# uC.net
KiCad netlist of a schematic drawn in Altium Designer
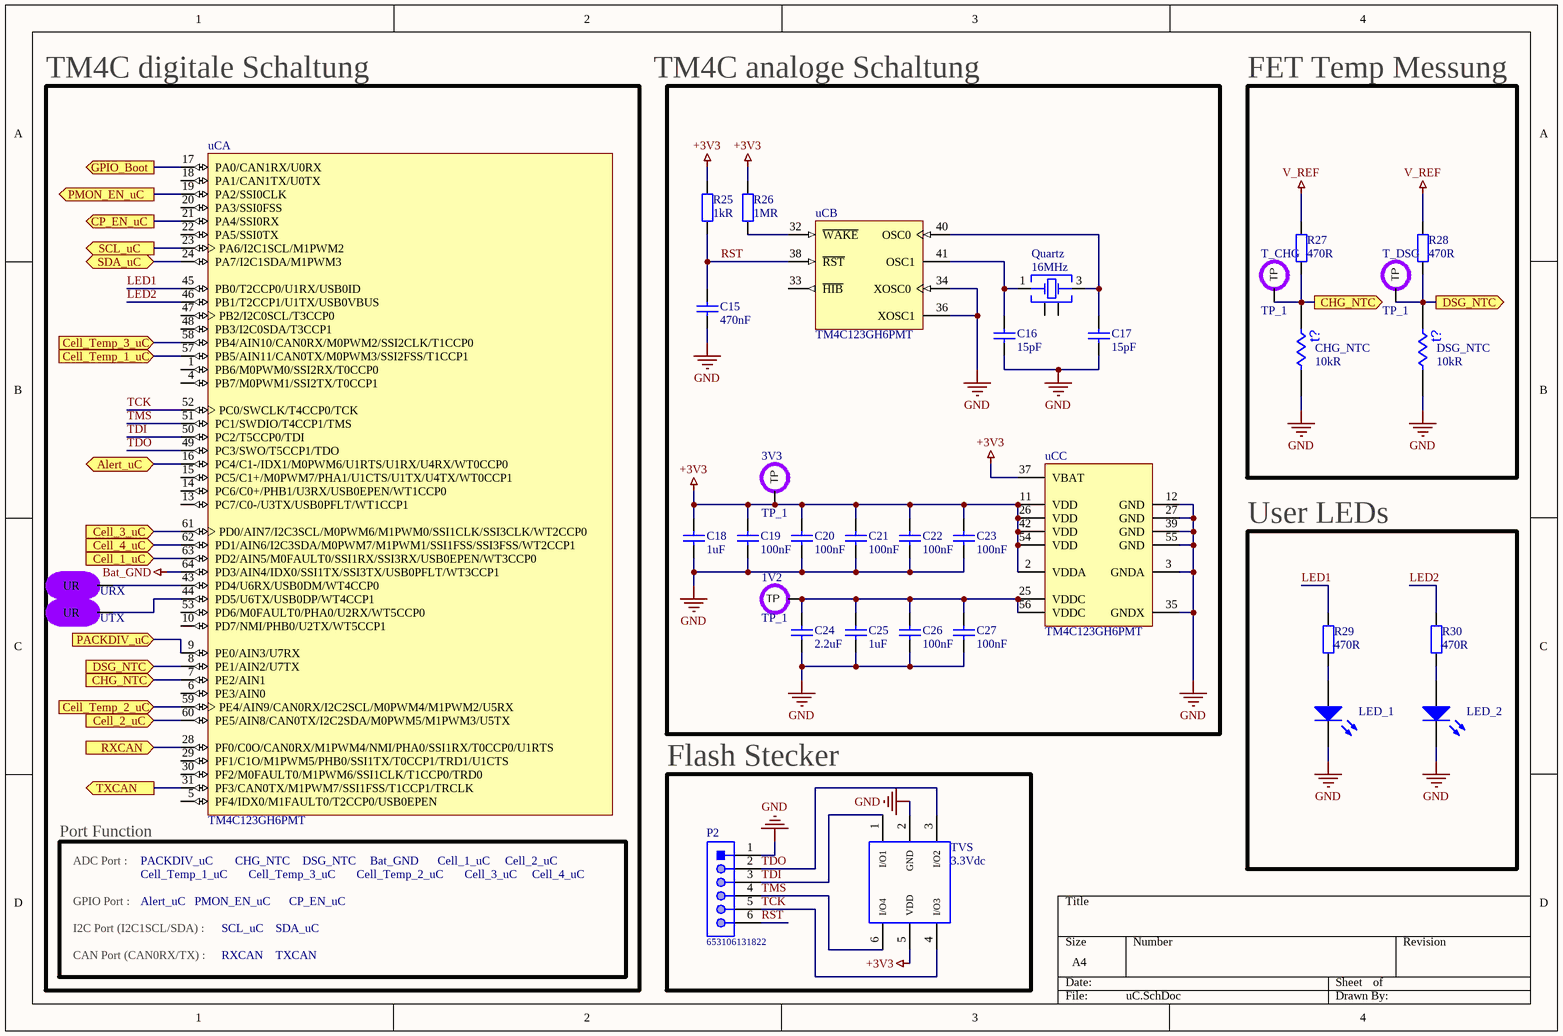
[diagram p0: uC.SchDoc]

(export (version "E")
  (design (tool "Eeschema 10.0.6"))
  (components
    (comp (ref "1V2")
      (value "TP_1")
      (footprint "Test point")
      (description "Power Supply for logical circuit")
      (libsource (lib "Schlib1") (part "Test point"))
    )
    (comp (ref "3V3")
      (value "TP_1")
      (footprint "Test point")
      (description "Power Supply for uC")
      (libsource (lib "Schlib1") (part "Test point"))
    )
    (comp (ref "C15")
      (value "470nF")
      (footprint "1608[0603]")
      (description "Capacitor")
      (fields (field (name "PUBLISHER") "Altium Limited"))
      (libsource (lib "Miscellaneous Devices") (part "Cap"))
    )
    (comp (ref "C16")
      (value "15pF")
      (footprint "1608[0603]")
      (description "Capacitor")
      (fields (field (name "PUBLISHER") "Altium Limited"))
      (libsource (lib "Miscellaneous Devices") (part "Cap"))
    )
    (comp (ref "C17")
      (value "15pF")
      (footprint "1608[0603]")
      (description "Capacitor")
      (fields (field (name "PUBLISHER") "Altium Limited"))
      (libsource (lib "Miscellaneous Devices") (part "Cap"))
    )
    (comp (ref "C18")
      (value "1uF")
      (footprint "1608[0603]")
      (description "Capacitor")
      (fields (field (name "PUBLISHER") "Altium Limited"))
      (libsource (lib "Miscellaneous Devices") (part "Cap"))
    )
    (comp (ref "C19")
      (value "100nF")
      (footprint "1608[0603]")
      (description "Capacitor")
      (fields (field (name "PUBLISHER") "Altium Limited"))
      (libsource (lib "Miscellaneous Devices") (part "Cap"))
    )
    (comp (ref "C20")
      (value "100nF")
      (footprint "1608[0603]")
      (description "Capacitor")
      (fields (field (name "PUBLISHER") "Altium Limited"))
      (libsource (lib "Miscellaneous Devices") (part "Cap"))
    )
    (comp (ref "C21")
      (value "100nF")
      (footprint "1608[0603]")
      (description "Capacitor")
      (fields (field (name "PUBLISHER") "Altium Limited"))
      (libsource (lib "Miscellaneous Devices") (part "Cap"))
    )
    (comp (ref "C22")
      (value "100nF")
      (footprint "1608[0603]")
      (description "Capacitor")
      (fields (field (name "PUBLISHER") "Altium Limited"))
      (libsource (lib "Miscellaneous Devices") (part "Cap"))
    )
    (comp (ref "C23")
      (value "100nF")
      (footprint "1608[0603]")
      (description "Capacitor")
      (fields (field (name "PUBLISHER") "Altium Limited"))
      (libsource (lib "Miscellaneous Devices") (part "Cap"))
    )
    (comp (ref "C24")
      (value "2.2uF")
      (footprint "1608[0603]")
      (description "Capacitor")
      (fields (field (name "PUBLISHER") "Altium Limited"))
      (libsource (lib "Miscellaneous Devices") (part "Cap"))
    )
    (comp (ref "C25")
      (value "1uF")
      (footprint "1608[0603]")
      (description "Capacitor")
      (fields (field (name "PUBLISHER") "Altium Limited"))
      (libsource (lib "Miscellaneous Devices") (part "Cap"))
    )
    (comp (ref "C26")
      (value "100nF")
      (footprint "1608[0603]")
      (description "Capacitor")
      (fields (field (name "PUBLISHER") "Altium Limited"))
      (libsource (lib "Miscellaneous Devices") (part "Cap"))
    )
    (comp (ref "C27")
      (value "100nF")
      (footprint "1608[0603]")
      (description "Capacitor")
      (fields (field (name "PUBLISHER") "Altium Limited"))
      (libsource (lib "Miscellaneous Devices") (part "Cap"))
    )
    (comp (ref "CHG_NTC")
      (value "10kR")
      (footprint "J1-0603")
      (description "Thermistor")
      (fields (field (name "PUBLISHER") "Altium Limited"))
      (libsource (lib "Miscellaneous Devices") (part "Res Thermal"))
    )
    (comp (ref "DSG_NTC")
      (value "10kR")
      (footprint "J1-0603")
      (description "Thermistor")
      (fields (field (name "PUBLISHER") "Altium Limited"))
      (libsource (lib "Miscellaneous Devices") (part "Res Thermal"))
    )
    (comp (ref "LED_1")
      (value "~")
      (footprint "1608[0603]")
      (description "Typical INFRARED GaAs LED")
      (fields (field (name "PUBLISHER") "Altium Limited"))
      (libsource (lib "Miscellaneous Devices") (part "LED0"))
    )
    (comp (ref "LED_2")
      (value "~")
      (footprint "1608[0603]")
      (description "Typical INFRARED GaAs LED")
      (fields (field (name "PUBLISHER") "Altium Limited"))
      (libsource (lib "Miscellaneous Devices") (part "LED0"))
    )
    (comp (ref "P2")
      (value "653106131822")
      (footprint "653106131822")
      (description "Male Shrouded Header WR-WTB, SMT, Right Angled, pitch 1.25 mm, 1 x 6 position")
      (fields (field (name "MANUFACTURER") "Wurth Elektronik") (field (name "PUBLISHER") "WurthElektronik"))
      (libsource (lib "Altium Content Vault") (part "WE-CN-1P-M-R6"))
    )
    (comp (ref "Quartz")
      (value "16MHz")
      (footprint "WE-XTAL_CFPX-180")
      (description "WE-XTAL Quartz Crystal, SMT, CFPX-180, 16MHz, +/-10ppm")
      (fields
        (field (name "MANUFACTURER PART NUMBER") "830108207109")
        (field (name "MANUFACTURER") "Wurth Elektronik")
      )
      (libsource (lib "Quartz Altium_WE-XTAL+(rev20c)") (part "830108207109"))
    )
    (comp (ref "R25")
      (value "1kR")
      (footprint "J1-0603")
      (description "Resistor")
      (fields (field (name "PUBLISHER") "Altium Limited"))
      (libsource (lib "") (part "Res2_1"))
    )
    (comp (ref "R26")
      (value "1MR")
      (footprint "J1-0603")
      (description "Resistor")
      (fields (field (name "PUBLISHER") "Altium Limited"))
      (libsource (lib "") (part "Res2_1"))
    )
    (comp (ref "R27")
      (value "470R")
      (footprint "J1-0603")
      (description "Resistor")
      (fields (field (name "PUBLISHER") "Altium Limited"))
      (libsource (lib "Miscellaneous Devices") (part "Res2"))
    )
    (comp (ref "R28")
      (value "470R")
      (footprint "J1-0603")
      (description "Resistor")
      (fields (field (name "PUBLISHER") "Altium Limited"))
      (libsource (lib "Miscellaneous Devices") (part "Res2"))
    )
    (comp (ref "R29")
      (value "470R")
      (footprint "J1-0603")
      (description "Resistor")
      (fields (field (name "PUBLISHER") "Altium Limited"))
      (libsource (lib "") (part "Res2_1"))
    )
    (comp (ref "R30")
      (value "470R")
      (footprint "J1-0603")
      (description "Resistor")
      (fields (field (name "PUBLISHER") "Altium Limited"))
      (libsource (lib "") (part "Res2_1"))
    )
    (comp (ref "TVS")
      (value "3.3Vdc")
      (footprint "WE-TVS_SOT23-6L")
      (description "WE-TVS TVS Diode - High Speed Series, SOT23-6L, 4+1Channel, 3.3Vdc")
      (fields
        (field (name "MANUFACTURER PART NUMBER") "824013")
        (field (name "MANUFACTURER") "Wurth Elektronik")
      )
      (libsource (lib "Altium_WE-TVS (rev20a)") (part "824013"))
    )
    (comp (ref "T_CHG")
      (value "TP_1")
      (footprint "Test point")
      (libsource (lib "Schlib1") (part "Test point"))
    )
    (comp (ref "T_DSG")
      (value "TP_1")
      (footprint "Test point")
      (libsource (lib "Schlib1") (part "Test point"))
    )
    (comp (ref "uC")
      (value "TM4C123GH6PMT")
      (footprint "PM0064A_L")
      (fields (field (name "MANUFACTURER") "Texas Instruments"))
      (libsource (lib "Altium Content Vault") (part "TI-TM4C123GH6PM-LQFP-64"))
    )
    (comp (ref "URX") (value "UR") (footprint "UR Pad") (libsource (lib "Schlib1") (part "UR Pad")))
    (comp (ref "UTX") (value "UR") (footprint "UR Pad") (libsource (lib "Schlib1") (part "UR Pad")))
  )
  (nets
    (net (code "1") (name "+3V3") (class "Default")
      (node (ref "3V3") (pin "1") (pinfunction "TP_1") (pintype "passive"))
      (node (ref "C18") (pin "1") (pinfunction "1_1") (pintype "passive"))
      (node (ref "C19") (pin "1") (pinfunction "1_1") (pintype "passive"))
      (node (ref "C20") (pin "1") (pinfunction "1_1") (pintype "passive"))
      (node (ref "C21") (pin "1") (pinfunction "1_1") (pintype "passive"))
      (node (ref "C22") (pin "1") (pinfunction "1_1") (pintype "passive"))
      (node (ref "C23") (pin "1") (pinfunction "1_1") (pintype "passive"))
      (node (ref "R25") (pin "1") (pinfunction "1_1") (pintype "passive"))
      (node (ref "R26") (pin "1") (pinfunction "1_1") (pintype "passive"))
      (node (ref "TVS") (pin "5") (pinfunction "VDD_5") (pintype "passive"))
      (node (ref "uC") (pin "11") (pinfunction "VDD_11") (pintype "power_in"))
      (node (ref "uC") (pin "2") (pinfunction "VDDA_2") (pintype "power_in"))
      (node (ref "uC") (pin "26") (pinfunction "VDD_26") (pintype "power_in"))
      (node (ref "uC") (pin "37") (pinfunction "VBAT_37") (pintype "power_in"))
      (node (ref "uC") (pin "42") (pinfunction "VDD_42") (pintype "power_in"))
      (node (ref "uC") (pin "54") (pinfunction "VDD_54") (pintype "power_in"))
    )
    (net (code "2") (name "/Alert_uC") (class "Default")
      (node (ref "uC") (pin "16") (pinfunction "PC4/C1-/IDX1/M0PWM6/U1RTS/U1RX/U4RX/WT0CCP0_16") (pintype "bidirectional"))
    )
    (net (code "3") (name "/CHG_NTC") (class "Default")
      (node (ref "CHG_NTC") (pin "1") (pinfunction "1_1") (pintype "passive"))
      (node (ref "R27") (pin "2") (pinfunction "2_2") (pintype "passive"))
      (node (ref "T_CHG") (pin "1") (pinfunction "TP_1") (pintype "passive"))
      (node (ref "uC") (pin "7") (pinfunction "PE2/AIN1_7") (pintype "bidirectional"))
    )
    (net (code "4") (name "/CP_EN_uC") (class "Default")
      (node (ref "uC") (pin "21") (pinfunction "PA4/SSI0RX_21") (pintype "bidirectional"))
    )
    (net (code "5") (name "/Cell_1_uC") (class "Default")
      (node (ref "uC") (pin "63") (pinfunction "PD2/AIN5/M0FAULT0/SSI1RX/SSI3RX/USB0EPEN/WT3CCP0_63") (pintype "bidirectional"))
    )
    (net (code "6") (name "/Cell_2_uC") (class "Default")
      (node (ref "uC") (pin "60") (pinfunction "PE5/AIN8/CAN0TX/I2C2SDA/M0PWM5/M1PWM3/U5TX_60") (pintype "bidirectional"))
    )
    (net (code "7") (name "/Cell_3_uC") (class "Default")
      (node (ref "uC") (pin "61") (pinfunction "PD0/AIN7/I2C3SCL/M0PWM6/M1PWM0/SSI1CLK/SSI3CLK/WT2CCP0_61") (pintype "bidirectional"))
    )
    (net (code "8") (name "/Cell_4_uC") (class "Default")
      (node (ref "uC") (pin "62") (pinfunction "PD1/AIN6/I2C3SDA/M0PWM7/M1PWM1/SSI1FSS/SSI3FSS/WT2CCP1_62") (pintype "bidirectional"))
    )
    (net (code "9") (name "/Cell_Temp_1_uC") (class "Default")
      (node (ref "uC") (pin "57") (pinfunction "PB5/AIN11/CAN0TX/M0PWM3/SSI2FSS/T1CCP1_57") (pintype "bidirectional"))
    )
    (net (code "10") (name "/Cell_Temp_2_uC") (class "Default")
      (node (ref "uC") (pin "59") (pinfunction "PE4/AIN9/CAN0RX/I2C2SCL/M0PWM4/M1PWM2/U5RX_59") (pintype "bidirectional"))
    )
    (net (code "11") (name "/Cell_Temp_3_uC") (class "Default")
      (node (ref "uC") (pin "58") (pinfunction "PB4/AIN10/CAN0RX/M0PWM2/SSI2CLK/T1CCP0_58") (pintype "bidirectional"))
    )
    (net (code "12") (name "/DSG_NTC") (class "Default")
      (node (ref "DSG_NTC") (pin "1") (pinfunction "1_1") (pintype "passive"))
      (node (ref "R28") (pin "2") (pinfunction "2_2") (pintype "passive"))
      (node (ref "T_DSG") (pin "1") (pinfunction "TP_1") (pintype "passive"))
      (node (ref "uC") (pin "8") (pinfunction "PE1/AIN2/U7TX_8") (pintype "bidirectional"))
    )
    (net (code "13") (name "/GPIO_Boot") (class "Default")
      (node (ref "uC") (pin "17") (pinfunction "PA0/CAN1RX/U0RX_17") (pintype "bidirectional"))
    )
    (net (code "14") (name "/LED1") (class "Default")
      (node (ref "R29") (pin "1") (pinfunction "1_1") (pintype "passive"))
      (node (ref "uC") (pin "45") (pinfunction "PB0/T2CCP0/U1RX/USB0ID_45") (pintype "bidirectional"))
    )
    (net (code "15") (name "/LED2") (class "Default")
      (node (ref "R30") (pin "1") (pinfunction "1_1") (pintype "passive"))
      (node (ref "uC") (pin "46") (pinfunction "PB1/T2CCP1/U1TX/USB0VBUS_46") (pintype "bidirectional"))
    )
    (net (code "16") (name "/PACKDIV_uC") (class "Default")
      (node (ref "uC") (pin "9") (pinfunction "PE0/AIN3/U7RX_9") (pintype "bidirectional"))
    )
    (net (code "17") (name "/PMON_EN_uC") (class "Default")
      (node (ref "uC") (pin "19") (pinfunction "PA2/SSI0CLK_19") (pintype "bidirectional"))
    )
    (net (code "18") (name "/RST") (class "Default")
      (node (ref "C15") (pin "1") (pinfunction "1_1") (pintype "passive"))
      (node (ref "P2") (pin "6") (pinfunction "6_6") (pintype "passive"))
      (node (ref "R25") (pin "2") (pinfunction "2_2") (pintype "passive"))
      (node (ref "uC") (pin "38") (pinfunction "~{RST}_38") (pintype "input"))
    )
    (net (code "19") (name "/RXCAN") (class "Default")
      (node (ref "uC") (pin "28") (pinfunction "PF0/C0O/CAN0RX/M1PWM4/NMI/PHA0/SSI1RX/T0CCP0/U1RTS_28") (pintype "bidirectional"))
    )
    (net (code "20") (name "/SCL_uC") (class "Default")
      (node (ref "uC") (pin "23") (pinfunction "PA6/I2C1SCL/M1PWM2_23") (pintype "bidirectional"))
    )
    (net (code "21") (name "/SDA_uC") (class "Default")
      (node (ref "uC") (pin "24") (pinfunction "PA7/I2C1SDA/M1PWM3_24") (pintype "bidirectional"))
    )
    (net (code "22") (name "/TCK") (class "Default")
      (node (ref "P2") (pin "5") (pinfunction "5_5") (pintype "passive"))
      (node (ref "TVS") (pin "4") (pinfunction "I/O3_4") (pintype "passive"))
      (node (ref "uC") (pin "52") (pinfunction "PC0/SWCLK/T4CCP0/TCK_52") (pintype "bidirectional"))
    )
    (net (code "23") (name "/TDI") (class "Default")
      (node (ref "P2") (pin "3") (pinfunction "3_3") (pintype "passive"))
      (node (ref "TVS") (pin "1") (pinfunction "I/O1_1") (pintype "passive"))
      (node (ref "uC") (pin "50") (pinfunction "PC2/T5CCP0/TDI_50") (pintype "bidirectional"))
    )
    (net (code "24") (name "/TDO") (class "Default")
      (node (ref "P2") (pin "2") (pinfunction "2_2") (pintype "passive"))
      (node (ref "TVS") (pin "3") (pinfunction "I/O2_3") (pintype "passive"))
      (node (ref "uC") (pin "49") (pinfunction "PC3/SWO/T5CCP1/TDO_49") (pintype "bidirectional"))
    )
    (net (code "25") (name "/TMS") (class "Default")
      (node (ref "P2") (pin "4") (pinfunction "4_4") (pintype "passive"))
      (node (ref "TVS") (pin "6") (pinfunction "I/O4_6") (pintype "passive"))
      (node (ref "uC") (pin "51") (pinfunction "PC1/SWDIO/T4CCP1/TMS_51") (pintype "bidirectional"))
    )
    (net (code "26") (name "/TXCAN") (class "Default")
      (node (ref "uC") (pin "31") (pinfunction "PF3/CAN0TX/M1PWM7/SSI1FSS/T1CCP1/TRCLK_31") (pintype "bidirectional"))
    )
    (net (code "27") (name "Bat_GND") (class "Default")
      (node (ref "uC") (pin "64") (pinfunction "PD3/AIN4/IDX0/SSI1TX/SSI3TX/USB0PFLT/WT3CCP1_64") (pintype "bidirectional"))
    )
    (net (code "28") (name "GND") (class "Default")
      (node (ref "C15") (pin "2") (pinfunction "2_2") (pintype "passive"))
      (node (ref "C16") (pin "2") (pinfunction "2_2") (pintype "passive"))
      (node (ref "C17") (pin "2") (pinfunction "2_2") (pintype "passive"))
      (node (ref "C18") (pin "2") (pinfunction "2_2") (pintype "passive"))
      (node (ref "C19") (pin "2") (pinfunction "2_2") (pintype "passive"))
      (node (ref "C20") (pin "2") (pinfunction "2_2") (pintype "passive"))
      (node (ref "C21") (pin "2") (pinfunction "2_2") (pintype "passive"))
      (node (ref "C22") (pin "2") (pinfunction "2_2") (pintype "passive"))
      (node (ref "C23") (pin "2") (pinfunction "2_2") (pintype "passive"))
      (node (ref "C24") (pin "2") (pinfunction "2_2") (pintype "passive"))
      (node (ref "C25") (pin "2") (pinfunction "2_2") (pintype "passive"))
      (node (ref "C26") (pin "2") (pinfunction "2_2") (pintype "passive"))
      (node (ref "C27") (pin "2") (pinfunction "2_2") (pintype "passive"))
      (node (ref "CHG_NTC") (pin "2") (pinfunction "2_2") (pintype "passive"))
      (node (ref "DSG_NTC") (pin "2") (pinfunction "2_2") (pintype "passive"))
      (node (ref "LED_1") (pin "2") (pinfunction "K_2") (pintype "passive"))
      (node (ref "LED_2") (pin "2") (pinfunction "K_2") (pintype "passive"))
      (node (ref "P2") (pin "1") (pinfunction "1_1") (pintype "passive"))
      (node (ref "TVS") (pin "2") (pinfunction "GND_2") (pintype "passive"))
      (node (ref "uC") (pin "12") (pinfunction "GND_12") (pintype "power_in"))
      (node (ref "uC") (pin "27") (pinfunction "GND_27") (pintype "power_in"))
      (node (ref "uC") (pin "3") (pinfunction "GNDA_3") (pintype "power_in"))
      (node (ref "uC") (pin "34") (pinfunction "XOSC0_34") (pintype "input"))
      (node (ref "uC") (pin "35") (pinfunction "GNDX_35") (pintype "power_in"))
      (node (ref "uC") (pin "36") (pinfunction "XOSC1_36") (pintype "passive"))
      (node (ref "uC") (pin "39") (pinfunction "GND_39") (pintype "power_in"))
      (node (ref "uC") (pin "55") (pinfunction "GND_55") (pintype "power_in"))
    )
    (net (code "29") (name "Net-(1V2-TP)") (class "Default")
      (node (ref "1V2") (pin "1") (pinfunction "TP_1") (pintype "passive"))
      (node (ref "C24") (pin "1") (pinfunction "1_1") (pintype "passive"))
      (node (ref "C25") (pin "1") (pinfunction "1_1") (pintype "passive"))
      (node (ref "C26") (pin "1") (pinfunction "1_1") (pintype "passive"))
      (node (ref "C27") (pin "1") (pinfunction "1_1") (pintype "passive"))
      (node (ref "uC") (pin "25") (pinfunction "VDDC_25") (pintype "power_in"))
      (node (ref "uC") (pin "56") (pinfunction "VDDC_56") (pintype "power_in"))
    )
    (net (code "30") (name "Net-(LED_1-A)") (class "Default")
      (node (ref "LED_1") (pin "1") (pinfunction "A_1") (pintype "passive"))
      (node (ref "R29") (pin "2") (pinfunction "2_2") (pintype "passive"))
    )
    (net (code "31") (name "Net-(LED_2-A)") (class "Default")
      (node (ref "LED_2") (pin "1") (pinfunction "A_1") (pintype "passive"))
      (node (ref "R30") (pin "2") (pinfunction "2_2") (pintype "passive"))
    )
    (net (code "32") (name "Net-(URX-UR)") (class "Default")
      (node (ref "URX") (pin "1") (pinfunction "UR_1") (pintype "passive"))
      (node (ref "uC") (pin "43") (pinfunction "PD4/U6RX/USB0DM/WT4CCP0_43") (pintype "bidirectional"))
    )
    (net (code "33") (name "Net-(UTX-UR)") (class "Default")
      (node (ref "UTX") (pin "1") (pinfunction "UR_1") (pintype "passive"))
      (node (ref "uC") (pin "44") (pinfunction "PD5/U6TX/USB0DP/WT4CCP1_44") (pintype "bidirectional"))
    )
    (net (code "34") (name "Net-(uCB-OSC0)") (class "Default")
      (node (ref "C17") (pin "1") (pinfunction "1_1") (pintype "passive"))
      (node (ref "Quartz") (pin "3") (pinfunction "Crystal_3") (pintype "passive"))
      (node (ref "uC") (pin "40") (pinfunction "OSC0_40") (pintype "input"))
    )
    (net (code "35") (name "Net-(uCB-OSC1)") (class "Default")
      (node (ref "C16") (pin "1") (pinfunction "1_1") (pintype "passive"))
      (node (ref "Quartz") (pin "1") (pinfunction "Crystal_1") (pintype "passive"))
      (node (ref "uC") (pin "41") (pinfunction "OSC1_41") (pintype "passive"))
    )
    (net (code "36") (name "Net-(uCB-~{WAKE})") (class "Default")
      (node (ref "R26") (pin "2") (pinfunction "2_2") (pintype "passive"))
      (node (ref "uC") (pin "32") (pinfunction "~{WAKE}_32") (pintype "input"))
    )
    (net (code "37") (name "V_REF") (class "Default")
      (node (ref "R27") (pin "1") (pinfunction "1_1") (pintype "passive"))
      (node (ref "R28") (pin "1") (pinfunction "1_1") (pintype "passive"))
    )
    (net (code "38") (name "unconnected-(Quartz-GND-Pad2)") (class "Default")
      (node (ref "Quartz") (pin "2") (pinfunction "GND_2") (pintype "passive"))
    )
    (net (code "39") (name "unconnected-(Quartz-GND-Pad4)") (class "Default")
      (node (ref "Quartz") (pin "4") (pinfunction "GND_4") (pintype "passive"))
    )
    (net (code "40") (name "unconnected-(uCA-PA1{slash}CAN1TX{slash}U0TX-Pad18)") (class "Default")
      (node (ref "uC") (pin "18") (pinfunction "PA1/CAN1TX/U0TX_18") (pintype "bidirectional"))
    )
    (net (code "41") (name "unconnected-(uCA-PA3{slash}SSI0FSS-Pad20)") (class "Default")
      (node (ref "uC") (pin "20") (pinfunction "PA3/SSI0FSS_20") (pintype "bidirectional"))
    )
    (net (code "42") (name "unconnected-(uCA-PA5{slash}SSI0TX-Pad22)") (class "Default")
      (node (ref "uC") (pin "22") (pinfunction "PA5/SSI0TX_22") (pintype "bidirectional"))
    )
    (net (code "43") (name "unconnected-(uCA-PB2{slash}I2C0SCL{slash}T3CCP0-Pad47)") (class "Default")
      (node (ref "uC") (pin "47") (pinfunction "PB2/I2C0SCL/T3CCP0_47") (pintype "bidirectional"))
    )
    (net (code "44") (name "unconnected-(uCA-PB3{slash}I2C0SDA{slash}T3CCP1-Pad48)") (class "Default")
      (node (ref "uC") (pin "48") (pinfunction "PB3/I2C0SDA/T3CCP1_48") (pintype "bidirectional"))
    )
    (net (code "45") (name "unconnected-(uCA-PB6{slash}M0PWM0{slash}SSI2RX{slash}T0CCP0-Pad1)") (class "Default")
      (node (ref "uC") (pin "1") (pinfunction "PB6/M0PWM0/SSI2RX/T0CCP0_1") (pintype "bidirectional"))
    )
    (net (code "46") (name "unconnected-(uCA-PB7{slash}M0PWM1{slash}SSI2TX{slash}T0CCP1-Pad4)") (class "Default")
      (node (ref "uC") (pin "4") (pinfunction "PB7/M0PWM1/SSI2TX/T0CCP1_4") (pintype "bidirectional"))
    )
    (net (code "47") (name "unconnected-(uCA-PC5{slash}C1+{slash}M0PWM7{slash}PHA1{slash}U1CTS{slash}U1TX{slash}U4TX{slash}WT0CCP1-Pad15)") (class "Default")
      (node (ref "uC") (pin "15") (pinfunction "PC5/C1+/M0PWM7/PHA1/U1CTS/U1TX/U4TX/WT0CCP1_15") (pintype "bidirectional"))
    )
    (net (code "48") (name "unconnected-(uCA-PC6{slash}C0+{slash}PHB1{slash}U3RX{slash}USB0EPEN{slash}WT1CCP0-Pad14)") (class "Default")
      (node (ref "uC") (pin "14") (pinfunction "PC6/C0+/PHB1/U3RX/USB0EPEN/WT1CCP0_14") (pintype "bidirectional"))
    )
    (net (code "49") (name "unconnected-(uCA-PC7{slash}C0-{slash}U3TX{slash}USB0PFLT{slash}WT1CCP1-Pad13)") (class "Default")
      (node (ref "uC") (pin "13") (pinfunction "PC7/C0-/U3TX/USB0PFLT/WT1CCP1_13") (pintype "bidirectional"))
    )
    (net (code "50") (name "unconnected-(uCA-PD6{slash}M0FAULT0{slash}PHA0{slash}U2RX{slash}WT5CCP0-Pad53)") (class "Default")
      (node (ref "uC") (pin "53") (pinfunction "PD6/M0FAULT0/PHA0/U2RX/WT5CCP0_53") (pintype "bidirectional"))
    )
    (net (code "51") (name "unconnected-(uCA-PD7{slash}NMI{slash}PHB0{slash}U2TX{slash}WT5CCP1-Pad10)") (class "Default")
      (node (ref "uC") (pin "10") (pinfunction "PD7/NMI/PHB0/U2TX/WT5CCP1_10") (pintype "bidirectional"))
    )
    (net (code "52") (name "unconnected-(uCA-PE3{slash}AIN0-Pad6)") (class "Default")
      (node (ref "uC") (pin "6") (pinfunction "PE3/AIN0_6") (pintype "bidirectional"))
    )
    (net (code "53") (name "unconnected-(uCA-PF1{slash}C1O{slash}M1PWM5{slash}PHB0{slash}SSI1TX{slash}T0CCP1{slash}TRD1{slash}U1CTS-Pad29)") (class "Default")
      (node (ref "uC") (pin "29") (pinfunction "PF1/C1O/M1PWM5/PHB0/SSI1TX/T0CCP1/TRD1/U1CTS_29") (pintype "bidirectional"))
    )
    (net (code "54") (name "unconnected-(uCA-PF2{slash}M0FAULT0{slash}M1PWM6{slash}SSI1CLK{slash}T1CCP0{slash}TRD0-Pad30)") (class "Default")
      (node (ref "uC") (pin "30") (pinfunction "PF2/M0FAULT0/M1PWM6/SSI1CLK/T1CCP0/TRD0_30") (pintype "bidirectional"))
    )
    (net (code "55") (name "unconnected-(uCA-PF4{slash}IDX0{slash}M1FAULT0{slash}T2CCP0{slash}USB0EPEN-Pad5)") (class "Default")
      (node (ref "uC") (pin "5") (pinfunction "PF4/IDX0/M1FAULT0/T2CCP0/USB0EPEN_5") (pintype "bidirectional"))
    )
    (net (code "56") (name "unconnected-(uCB-~{HIB}-Pad33)") (class "Default")
      (node (ref "uC") (pin "33") (pinfunction "~{HIB}_33") (pintype "output"))
    )
  )
)
